# PAD.net
KiCad netlist of a schematic drawn in EAGLE
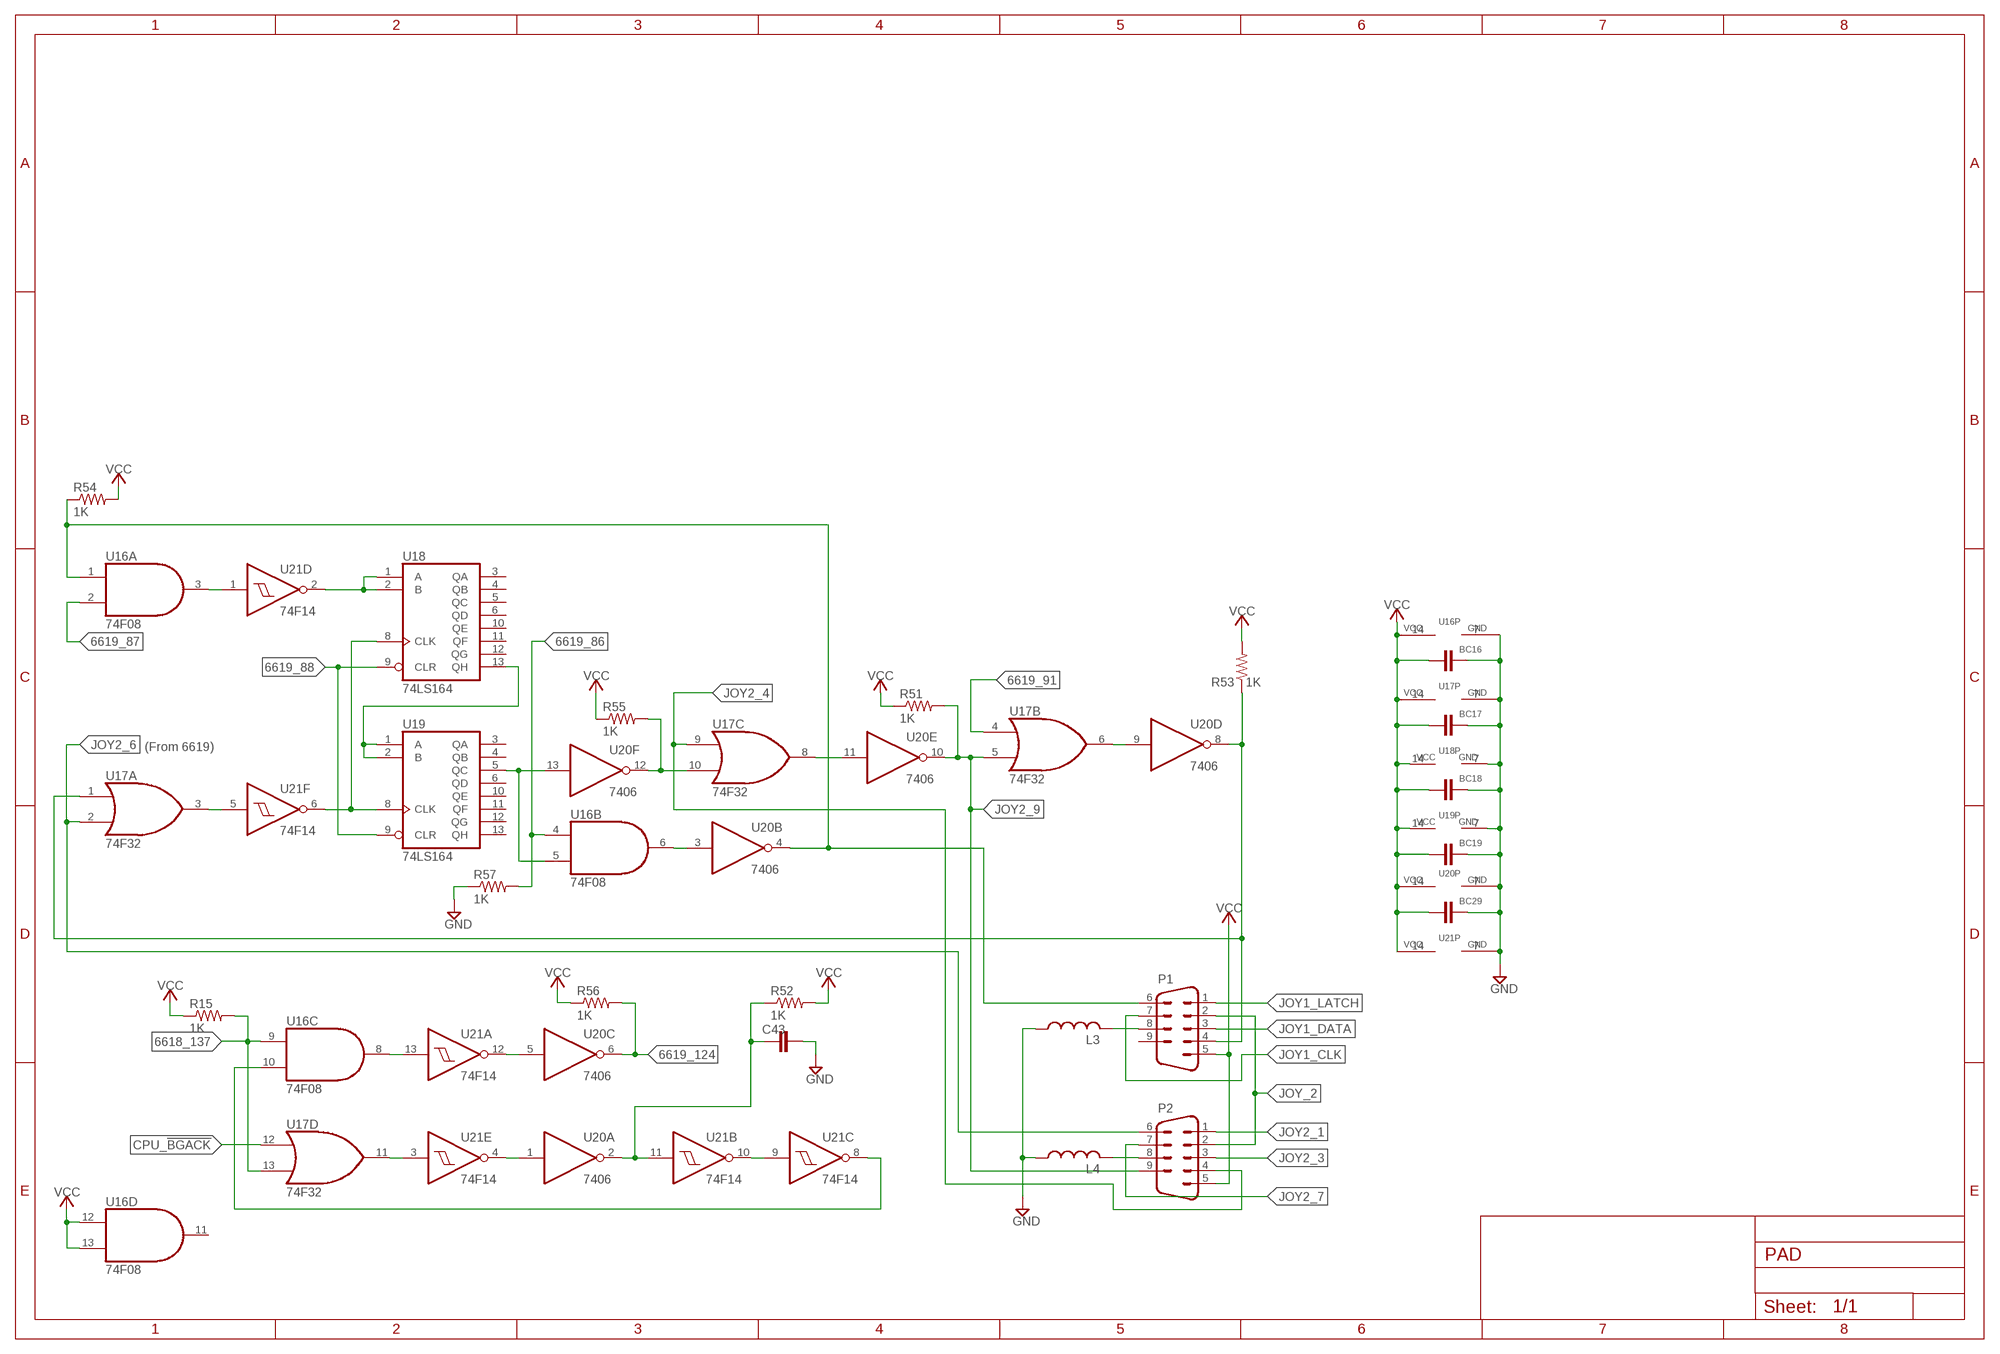
[diagram p0: schematic, sheet 1]

(export (version "E")
  (design (tool "Eeschema 10.0.6"))
  (components
    (comp (ref "BC16")
      (value "C-EUC0805")
      (footprint "eagle-import:C0805")
      (libsource (lib "eagle-import") (part "C-EUC0805"))
    )
    (comp (ref "BC17")
      (value "C-EUC0805")
      (footprint "eagle-import:C0805")
      (libsource (lib "eagle-import") (part "C-EUC0805"))
    )
    (comp (ref "BC18")
      (value "C-EUC0805")
      (footprint "eagle-import:C0805")
      (libsource (lib "eagle-import") (part "C-EUC0805"))
    )
    (comp (ref "BC19")
      (value "C-EUC0805")
      (footprint "eagle-import:C0805")
      (libsource (lib "eagle-import") (part "C-EUC0805"))
    )
    (comp (ref "BC29")
      (value "C-EUC0805")
      (footprint "eagle-import:C0805")
      (libsource (lib "eagle-import") (part "C-EUC0805"))
    )
    (comp (ref "C43")
      (value "C-EUC0805")
      (footprint "eagle-import:C0805")
      (libsource (lib "eagle-import") (part "C-EUC0805"))
    )
    (comp (ref "L3")
      (value "L-US0204/7")
      (footprint "eagle-import:0204_7")
      (libsource (lib "eagle-import") (part "L-US0204/7"))
    )
    (comp (ref "L4")
      (value "L-US0204/7")
      (footprint "eagle-import:0204_7")
      (libsource (lib "eagle-import") (part "L-US0204/7"))
    )
    (comp (ref "P1")
      (value "GAMEPAD_CONNECTOR")
      (footprint "eagle-import:PAD_CONNECTOR")
      (libsource (lib "eagle-import") (part "GAMEPAD_CONNECTOR"))
    )
    (comp (ref "P2")
      (value "GAMEPAD_CONNECTOR")
      (footprint "eagle-import:PAD_CONNECTOR")
      (libsource (lib "eagle-import") (part "GAMEPAD_CONNECTOR"))
    )
    (comp (ref "R15")
      (value "1K")
      (footprint "eagle-import:R0805")
      (libsource (lib "eagle-import") (part "R-US_R0805"))
    )
    (comp (ref "R51")
      (value "1K")
      (footprint "eagle-import:R0805")
      (libsource (lib "eagle-import") (part "R-US_R0805"))
    )
    (comp (ref "R52")
      (value "1K")
      (footprint "eagle-import:R0805")
      (libsource (lib "eagle-import") (part "R-US_R0805"))
    )
    (comp (ref "R53")
      (value "1K")
      (footprint "eagle-import:R0805")
      (libsource (lib "eagle-import") (part "R-US_R0805"))
    )
    (comp (ref "R54")
      (value "1K")
      (footprint "eagle-import:R0805")
      (libsource (lib "eagle-import") (part "R-US_R0805"))
    )
    (comp (ref "R55")
      (value "1K")
      (footprint "eagle-import:R0805")
      (libsource (lib "eagle-import") (part "R-US_R0805"))
    )
    (comp (ref "R56")
      (value "1K")
      (footprint "eagle-import:R0805")
      (libsource (lib "eagle-import") (part "R-US_R0805"))
    )
    (comp (ref "R57")
      (value "1K")
      (footprint "eagle-import:R0805")
      (libsource (lib "eagle-import") (part "R-US_R0805"))
    )
    (comp (ref "U16")
      (value "74F08")
      (footprint "eagle-import:DIL14")
      (libsource (lib "eagle-import") (part "7408NLS"))
    )
    (comp (ref "U17")
      (value "74F32")
      (footprint "eagle-import:DIL14")
      (libsource (lib "eagle-import") (part "7432NLS"))
    )
    (comp (ref "U18")
      (value "74LS164")
      (footprint "eagle-import:DIL14")
      (libsource (lib "eagle-import") (part "74164NLS"))
    )
    (comp (ref "U19")
      (value "74LS164")
      (footprint "eagle-import:DIL14")
      (libsource (lib "eagle-import") (part "74164NLS"))
    )
    (comp (ref "U20")
      (value "7406")
      (footprint "eagle-import:DIL14")
      (libsource (lib "eagle-import") (part "7406N"))
    )
    (comp (ref "U21")
      (value "74F14")
      (footprint "eagle-import:DIL14")
      (libsource (lib "eagle-import") (part "7414NLS"))
    )
  )
  (nets
    (net (code "1") (name "/CPU_~{BGACK}") (class "Default")
      (node (ref "U17") (pin "12") (pinfunction "I0_12") (pintype "input"))
    )
    (net (code "2") (name "6618_137") (class "Default")
      (node (ref "R15") (pin "2") (pinfunction "2_2") (pintype "passive"))
      (node (ref "U16") (pin "9") (pinfunction "I0_9") (pintype "input"))
      (node (ref "U17") (pin "13") (pinfunction "I1_13") (pintype "input"))
    )
    (net (code "3") (name "6619_86") (class "Default")
      (node (ref "R57") (pin "2") (pinfunction "2_2") (pintype "passive"))
      (node (ref "U16") (pin "4") (pinfunction "I0_4") (pintype "input"))
    )
    (net (code "4") (name "6619_87") (class "Default")
      (node (ref "U16") (pin "2") (pinfunction "I1_2") (pintype "input"))
    )
    (net (code "5") (name "6619_88") (class "Default")
      (node (ref "U18") (pin "9") (pinfunction "CLR_9") (pintype "input"))
      (node (ref "U19") (pin "9") (pinfunction "CLR_9") (pintype "input"))
    )
    (net (code "6") (name "6619_91") (class "Default")
      (node (ref "U17") (pin "4") (pinfunction "I0_4") (pintype "input"))
    )
    (net (code "7") (name "6619_124") (class "Default")
      (node (ref "R56") (pin "2") (pinfunction "2_2") (pintype "passive"))
      (node (ref "U20") (pin "6") (pinfunction "O_6") (pintype "open_collector"))
    )
    (net (code "8") (name "GND") (class "Default")
      (node (ref "BC16") (pin "2") (pinfunction "2_2") (pintype "passive"))
      (node (ref "BC17") (pin "2") (pinfunction "2_2") (pintype "passive"))
      (node (ref "BC18") (pin "2") (pinfunction "2_2") (pintype "passive"))
      (node (ref "BC19") (pin "2") (pinfunction "2_2") (pintype "passive"))
      (node (ref "BC29") (pin "2") (pinfunction "2_2") (pintype "passive"))
      (node (ref "C43") (pin "2") (pinfunction "2_2") (pintype "passive"))
      (node (ref "L3") (pin "1") (pinfunction "1_1") (pintype "passive"))
      (node (ref "L4") (pin "1") (pinfunction "1_1") (pintype "passive"))
      (node (ref "R57") (pin "1") (pinfunction "1_1") (pintype "passive"))
      (node (ref "U16") (pin "7") (pinfunction "GND_7") (pintype "power_in"))
      (node (ref "U17") (pin "7") (pinfunction "GND_7") (pintype "power_in"))
      (node (ref "U18") (pin "7") (pinfunction "GND_7") (pintype "power_in"))
      (node (ref "U19") (pin "7") (pinfunction "GND_7") (pintype "power_in"))
      (node (ref "U20") (pin "7") (pinfunction "GND_7") (pintype "power_in"))
      (node (ref "U21") (pin "7") (pinfunction "GND_7") (pintype "power_in"))
    )
    (net (code "9") (name "JOY1_CLK") (class "Default")
      (node (ref "P1") (pin "7") (pinfunction "7_7") (pintype "passive"))
    )
    (net (code "10") (name "JOY1_DATA") (class "Default")
      (node (ref "P1") (pin "3") (pinfunction "3_3") (pintype "passive"))
    )
    (net (code "11") (name "JOY1_LATCH") (class "Default")
      (node (ref "P1") (pin "1") (pinfunction "1_1") (pintype "passive"))
    )
    (net (code "12") (name "JOY2_1") (class "Default")
      (node (ref "P2") (pin "1") (pinfunction "1_1") (pintype "passive"))
    )
    (net (code "13") (name "JOY2_3") (class "Default")
      (node (ref "P2") (pin "3") (pinfunction "3_3") (pintype "passive"))
    )
    (net (code "14") (name "JOY2_4") (class "Default")
      (node (ref "P2") (pin "4") (pinfunction "4_4") (pintype "passive"))
      (node (ref "U17") (pin "9") (pinfunction "I0_9") (pintype "input"))
    )
    (net (code "15") (name "JOY2_6") (class "Default")
      (node (ref "P2") (pin "6") (pinfunction "6_6") (pintype "passive"))
      (node (ref "U17") (pin "2") (pinfunction "I1_2") (pintype "input"))
    )
    (net (code "16") (name "JOY2_7") (class "Default")
      (node (ref "P2") (pin "7") (pinfunction "7_7") (pintype "passive"))
    )
    (net (code "17") (name "JOY2_9") (class "Default")
      (node (ref "P2") (pin "9") (pinfunction "9_9") (pintype "passive"))
      (node (ref "R51") (pin "2") (pinfunction "2_2") (pintype "passive"))
      (node (ref "U17") (pin "5") (pinfunction "I1_5") (pintype "input"))
      (node (ref "U20") (pin "10") (pinfunction "O_10") (pintype "open_collector"))
    )
    (net (code "18") (name "JOY_2") (class "Default")
      (node (ref "P1") (pin "2") (pinfunction "2_2") (pintype "passive"))
      (node (ref "P2") (pin "2") (pinfunction "2_2") (pintype "passive"))
    )
    (net (code "19") (name "Net-(P1-GND)") (class "Default")
      (node (ref "L3") (pin "2") (pinfunction "2_2") (pintype "passive"))
      (node (ref "P1") (pin "8") (pinfunction "GND_8") (pintype "power_in"))
    )
    (net (code "20") (name "Net-(P2-GND)") (class "Default")
      (node (ref "L4") (pin "2") (pinfunction "2_2") (pintype "passive"))
      (node (ref "P2") (pin "8") (pinfunction "GND_8") (pintype "power_in"))
    )
    (net (code "21") (name "Net-(U16A-I0)") (class "Default")
      (node (ref "P1") (pin "6") (pinfunction "6_6") (pintype "passive"))
      (node (ref "R54") (pin "1") (pinfunction "1_1") (pintype "passive"))
      (node (ref "U16") (pin "1") (pinfunction "I0_1") (pintype "input"))
      (node (ref "U20") (pin "4") (pinfunction "O_4") (pintype "open_collector"))
    )
    (net (code "22") (name "Net-(U16A-O)") (class "Default")
      (node (ref "U16") (pin "3") (pinfunction "O_3") (pintype "output"))
      (node (ref "U21") (pin "1") (pinfunction "I_1") (pintype "input"))
    )
    (net (code "23") (name "Net-(U16B-I1)") (class "Default")
      (node (ref "U16") (pin "5") (pinfunction "I1_5") (pintype "input"))
      (node (ref "U19") (pin "5") (pinfunction "QC_5") (pintype "output"))
      (node (ref "U20") (pin "13") (pinfunction "I_13") (pintype "input"))
    )
    (net (code "24") (name "Net-(U16B-O)") (class "Default")
      (node (ref "U16") (pin "6") (pinfunction "O_6") (pintype "output"))
      (node (ref "U20") (pin "3") (pinfunction "I_3") (pintype "input"))
    )
    (net (code "25") (name "Net-(U16C-I1)") (class "Default")
      (node (ref "U16") (pin "10") (pinfunction "I1_10") (pintype "input"))
      (node (ref "U21") (pin "8") (pinfunction "O_8") (pintype "output"))
    )
    (net (code "26") (name "Net-(U16C-O)") (class "Default")
      (node (ref "U16") (pin "8") (pinfunction "O_8") (pintype "output"))
      (node (ref "U21") (pin "13") (pinfunction "I_13") (pintype "input"))
    )
    (net (code "27") (name "Net-(U17A-I0)") (class "Default")
      (node (ref "P1") (pin "4") (pinfunction "4_4") (pintype "passive"))
      (node (ref "R53") (pin "1") (pinfunction "1_1") (pintype "passive"))
      (node (ref "U17") (pin "1") (pinfunction "I0_1") (pintype "input"))
      (node (ref "U20") (pin "8") (pinfunction "O_8") (pintype "open_collector"))
    )
    (net (code "28") (name "Net-(U17A-O)") (class "Default")
      (node (ref "U17") (pin "3") (pinfunction "O_3") (pintype "output"))
      (node (ref "U21") (pin "5") (pinfunction "I_5") (pintype "input"))
    )
    (net (code "29") (name "Net-(U17B-O)") (class "Default")
      (node (ref "U17") (pin "6") (pinfunction "O_6") (pintype "output"))
      (node (ref "U20") (pin "9") (pinfunction "I_9") (pintype "input"))
    )
    (net (code "30") (name "Net-(U17C-I1)") (class "Default")
      (node (ref "R55") (pin "2") (pinfunction "2_2") (pintype "passive"))
      (node (ref "U17") (pin "10") (pinfunction "I1_10") (pintype "input"))
      (node (ref "U20") (pin "12") (pinfunction "O_12") (pintype "open_collector"))
    )
    (net (code "31") (name "Net-(U17C-O)") (class "Default")
      (node (ref "U17") (pin "8") (pinfunction "O_8") (pintype "output"))
      (node (ref "U20") (pin "11") (pinfunction "I_11") (pintype "input"))
    )
    (net (code "32") (name "Net-(U17D-O)") (class "Default")
      (node (ref "U17") (pin "11") (pinfunction "O_11") (pintype "output"))
      (node (ref "U21") (pin "3") (pinfunction "I_3") (pintype "input"))
    )
    (net (code "33") (name "Net-(U18A-A)") (class "Default")
      (node (ref "U18") (pin "1") (pinfunction "A_1") (pintype "input"))
      (node (ref "U18") (pin "2") (pinfunction "B_2") (pintype "input"))
      (node (ref "U21") (pin "2") (pinfunction "O_2") (pintype "output"))
    )
    (net (code "34") (name "Net-(U18A-CLK)") (class "Default")
      (node (ref "U18") (pin "8") (pinfunction "CLK_8") (pintype "input"))
      (node (ref "U19") (pin "8") (pinfunction "CLK_8") (pintype "input"))
      (node (ref "U21") (pin "6") (pinfunction "O_6") (pintype "output"))
    )
    (net (code "35") (name "Net-(U18A-QH)") (class "Default")
      (node (ref "U18") (pin "13") (pinfunction "QH_13") (pintype "output"))
      (node (ref "U19") (pin "1") (pinfunction "A_1") (pintype "input"))
      (node (ref "U19") (pin "2") (pinfunction "B_2") (pintype "input"))
    )
    (net (code "36") (name "Net-(U20A-I)") (class "Default")
      (node (ref "U20") (pin "1") (pinfunction "I_1") (pintype "input"))
      (node (ref "U21") (pin "4") (pinfunction "O_4") (pintype "output"))
    )
    (net (code "37") (name "Net-(U20A-O)") (class "Default")
      (node (ref "C43") (pin "1") (pinfunction "1_1") (pintype "passive"))
      (node (ref "R52") (pin "1") (pinfunction "1_1") (pintype "passive"))
      (node (ref "U20") (pin "2") (pinfunction "O_2") (pintype "open_collector"))
      (node (ref "U21") (pin "11") (pinfunction "I_11") (pintype "input"))
    )
    (net (code "38") (name "Net-(U20C-I)") (class "Default")
      (node (ref "U20") (pin "5") (pinfunction "I_5") (pintype "input"))
      (node (ref "U21") (pin "12") (pinfunction "O_12") (pintype "output"))
    )
    (net (code "39") (name "Net-(U21B-O)") (class "Default")
      (node (ref "U21") (pin "10") (pinfunction "O_10") (pintype "output"))
      (node (ref "U21") (pin "9") (pinfunction "I_9") (pintype "input"))
    )
    (net (code "40") (name "VCC") (class "Default")
      (node (ref "BC16") (pin "1") (pinfunction "1_1") (pintype "passive"))
      (node (ref "BC17") (pin "1") (pinfunction "1_1") (pintype "passive"))
      (node (ref "BC18") (pin "1") (pinfunction "1_1") (pintype "passive"))
      (node (ref "BC19") (pin "1") (pinfunction "1_1") (pintype "passive"))
      (node (ref "BC29") (pin "1") (pinfunction "1_1") (pintype "passive"))
      (node (ref "P1") (pin "5") (pinfunction "VCC_5") (pintype "power_in"))
      (node (ref "P2") (pin "5") (pinfunction "VCC_5") (pintype "power_in"))
      (node (ref "R15") (pin "1") (pinfunction "1_1") (pintype "passive"))
      (node (ref "R51") (pin "1") (pinfunction "1_1") (pintype "passive"))
      (node (ref "R52") (pin "2") (pinfunction "2_2") (pintype "passive"))
      (node (ref "R53") (pin "2") (pinfunction "2_2") (pintype "passive"))
      (node (ref "R54") (pin "2") (pinfunction "2_2") (pintype "passive"))
      (node (ref "R55") (pin "1") (pinfunction "1_1") (pintype "passive"))
      (node (ref "R56") (pin "1") (pinfunction "1_1") (pintype "passive"))
      (node (ref "U16") (pin "12") (pinfunction "I0_12") (pintype "input"))
      (node (ref "U16") (pin "13") (pinfunction "I1_13") (pintype "input"))
      (node (ref "U16") (pin "14") (pinfunction "VCC_14") (pintype "power_in"))
      (node (ref "U17") (pin "14") (pinfunction "VCC_14") (pintype "power_in"))
      (node (ref "U18") (pin "14") (pinfunction "VCC_14") (pintype "power_in"))
      (node (ref "U19") (pin "14") (pinfunction "VCC_14") (pintype "power_in"))
      (node (ref "U20") (pin "14") (pinfunction "VCC_14") (pintype "power_in"))
      (node (ref "U21") (pin "14") (pinfunction "VCC_14") (pintype "power_in"))
    )
    (net (code "41") (name "unconnected-(P1-Pad9)") (class "Default")
      (node (ref "P1") (pin "9") (pinfunction "9_9") (pintype "passive"))
    )
    (net (code "42") (name "unconnected-(U16D-O-Pad11)") (class "Default")
      (node (ref "U16") (pin "11") (pinfunction "O_11") (pintype "output"))
    )
    (net (code "43") (name "unconnected-(U18A-QA-Pad3)") (class "Default")
      (node (ref "U18") (pin "3") (pinfunction "QA_3") (pintype "output"))
    )
    (net (code "44") (name "unconnected-(U18A-QB-Pad4)") (class "Default")
      (node (ref "U18") (pin "4") (pinfunction "QB_4") (pintype "output"))
    )
    (net (code "45") (name "unconnected-(U18A-QC-Pad5)") (class "Default")
      (node (ref "U18") (pin "5") (pinfunction "QC_5") (pintype "output"))
    )
    (net (code "46") (name "unconnected-(U18A-QD-Pad6)") (class "Default")
      (node (ref "U18") (pin "6") (pinfunction "QD_6") (pintype "output"))
    )
    (net (code "47") (name "unconnected-(U18A-QE-Pad10)") (class "Default")
      (node (ref "U18") (pin "10") (pinfunction "QE_10") (pintype "output"))
    )
    (net (code "48") (name "unconnected-(U18A-QF-Pad11)") (class "Default")
      (node (ref "U18") (pin "11") (pinfunction "QF_11") (pintype "output"))
    )
    (net (code "49") (name "unconnected-(U18A-QG-Pad12)") (class "Default")
      (node (ref "U18") (pin "12") (pinfunction "QG_12") (pintype "output"))
    )
    (net (code "50") (name "unconnected-(U19A-QA-Pad3)") (class "Default")
      (node (ref "U19") (pin "3") (pinfunction "QA_3") (pintype "output"))
    )
    (net (code "51") (name "unconnected-(U19A-QB-Pad4)") (class "Default")
      (node (ref "U19") (pin "4") (pinfunction "QB_4") (pintype "output"))
    )
    (net (code "52") (name "unconnected-(U19A-QD-Pad6)") (class "Default")
      (node (ref "U19") (pin "6") (pinfunction "QD_6") (pintype "output"))
    )
    (net (code "53") (name "unconnected-(U19A-QE-Pad10)") (class "Default")
      (node (ref "U19") (pin "10") (pinfunction "QE_10") (pintype "output"))
    )
    (net (code "54") (name "unconnected-(U19A-QF-Pad11)") (class "Default")
      (node (ref "U19") (pin "11") (pinfunction "QF_11") (pintype "output"))
    )
    (net (code "55") (name "unconnected-(U19A-QG-Pad12)") (class "Default")
      (node (ref "U19") (pin "12") (pinfunction "QG_12") (pintype "output"))
    )
    (net (code "56") (name "unconnected-(U19A-QH-Pad13)") (class "Default")
      (node (ref "U19") (pin "13") (pinfunction "QH_13") (pintype "output"))
    )
  )
)
